# light_sensor_basic_finished.net
KiCad netlist of a schematic drawn in EAGLE
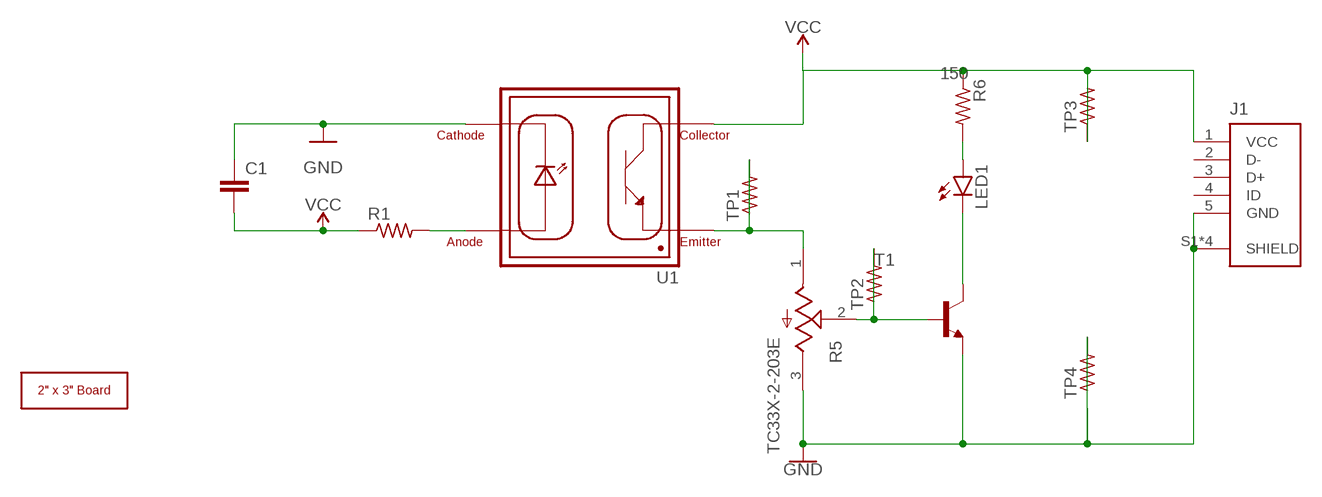
[diagram p0: schematic, sheet 1]

(export (version "E")
  (design (tool "Eeschema 10.0.6"))
  (components
    (comp (ref "C1")
      (value "1 uF")
      (footprint "eagle-import:C1206")
      (libsource (lib "eagle-import") (part "C-EUC1206"))
    )
    (comp (ref "J1")
      (value "UJ2-MIBH-G-SMT-TR")
      (footprint "eagle-import:CUI_UJ2-MIBH-G-SMT-TR")
      (fields (field (name "MANUFACTURER") "CUI"))
      (libsource (lib "eagle-import") (part "UJ2-MIBH-G-SMT-TR"))
    )
    (comp (ref "LED1")
      (value "LEDSML0805")
      (footprint "eagle-import:SML0805")
      (libsource (lib "eagle-import") (part "LEDSML0805"))
    )
    (comp (ref "R1")
      (value "R-US_M1206")
      (footprint "eagle-import:M1206")
      (libsource (lib "eagle-import") (part "R-US_M1206"))
    )
    (comp (ref "R5")
      (value "TC33X-2-203E")
      (footprint "eagle-import:TRIM_TC33X-2-203E")
      (fields (field (name "DIGIKEY_PART_NUMBER") "TC33X-2-203ETR-ND") (field (name "MF") "Bourns"))
      (libsource (lib "eagle-import") (part "TC33X-2-203E"))
    )
    (comp (ref "R6")
      (value "150")
      (footprint "eagle-import:M0805")
      (libsource (lib "eagle-import") (part "R-US_M0805"))
    )
    (comp (ref "T1")
      (value "-NPN-SOT23-EBC")
      (footprint "eagle-import:SOT23-EBC")
      (libsource (lib "eagle-import") (part "-NPN-SOT23-EBC"))
    )
    (comp (ref "TP1")
      (value "R-US_M1206")
      (footprint "eagle-import:M1206")
      (libsource (lib "eagle-import") (part "R-US_M1206"))
    )
    (comp (ref "TP2")
      (value "R-US_M1206")
      (footprint "eagle-import:M1206")
      (libsource (lib "eagle-import") (part "R-US_M1206"))
    )
    (comp (ref "TP3")
      (value "R-US_M1206")
      (footprint "eagle-import:M1206")
      (libsource (lib "eagle-import") (part "R-US_M1206"))
    )
    (comp (ref "TP4")
      (value "R-US_M1206")
      (footprint "eagle-import:M1206")
      (libsource (lib "eagle-import") (part "R-US_M1206"))
    )
    (comp (ref "U$1")
      (value "2X3_BOARD_V2")
      (footprint "eagle-import:2X3_BOARD_V2")
      (libsource (lib "eagle-import") (part "2X3_BOARD_V2"))
    )
    (comp (ref "U1")
      (value "VCNT2020")
      (footprint "eagle-import:XDCR_VCNT2020")
      (fields (field (name "DIGIKEY_PART_NUMBER") "VCNT2020TR-ND") (field (name "MF") "Vishay"))
      (libsource (lib "eagle-import") (part "VCNT2020"))
    )
  )
  (nets
    (net (code "1") (name "GND") (class "Default")
      (node (ref "C1") (pin "1") (pinfunction "1_1") (pintype "passive"))
      (node (ref "J1") (pin "5") (pinfunction "GND_5") (pintype "power_in"))
      (node (ref "J1") (pin "S1") (pinfunction "SHIELD_S1") (pintype "passive"))
      (node (ref "J1") (pin "S2") (pinfunction "SHIELD_S2") (pintype "passive"))
      (node (ref "J1") (pin "S3") (pinfunction "SHIELD_S3") (pintype "passive"))
      (node (ref "J1") (pin "S4") (pinfunction "SHIELD_S4") (pintype "passive"))
      (node (ref "R5") (pin "3") (pinfunction "CW_3") (pintype "passive"))
      (node (ref "T1") (pin "E") (pinfunction "E_E") (pintype "passive"))
      (node (ref "TP4") (pin "1") (pinfunction "1_1") (pintype "passive"))
      (node (ref "TP4") (pin "2") (pinfunction "2_2") (pintype "passive"))
      (node (ref "U1") (pin "4") (pinfunction "CATHODE_4") (pintype "passive"))
    )
    (net (code "2") (name "Net-(LED1-PadA)") (class "Default")
      (node (ref "LED1") (pin "A") (pinfunction "A_A") (pintype "passive"))
      (node (ref "R6") (pin "2") (pinfunction "2_2") (pintype "passive"))
    )
    (net (code "3") (name "Net-(LED1-PadC)") (class "Default")
      (node (ref "LED1") (pin "C") (pinfunction "C_C") (pintype "passive"))
      (node (ref "T1") (pin "C") (pinfunction "C_C") (pintype "passive"))
    )
    (net (code "4") (name "Net-(R5-CCW)") (class "Default")
      (node (ref "R5") (pin "1") (pinfunction "CCW_1") (pintype "passive"))
      (node (ref "TP1") (pin "1") (pinfunction "1_1") (pintype "passive"))
      (node (ref "TP1") (pin "2") (pinfunction "2_2") (pintype "passive"))
      (node (ref "U1") (pin "1") (pinfunction "EMITTER_1") (pintype "passive"))
    )
    (net (code "5") (name "Net-(R5-W)") (class "Default")
      (node (ref "R5") (pin "2") (pinfunction "W_2") (pintype "passive"))
      (node (ref "T1") (pin "B") (pinfunction "B_B") (pintype "passive"))
      (node (ref "TP2") (pin "1") (pinfunction "1_1") (pintype "passive"))
      (node (ref "TP2") (pin "2") (pinfunction "2_2") (pintype "passive"))
    )
    (net (code "6") (name "Net-(U1-ANODE)") (class "Default")
      (node (ref "R1") (pin "2") (pinfunction "2_2") (pintype "passive"))
      (node (ref "U1") (pin "3") (pinfunction "ANODE_3") (pintype "passive"))
    )
    (net (code "7") (name "VCC") (class "Default")
      (node (ref "C1") (pin "2") (pinfunction "2_2") (pintype "passive"))
      (node (ref "J1") (pin "1") (pinfunction "VCC_1") (pintype "power_in"))
      (node (ref "R1") (pin "1") (pinfunction "1_1") (pintype "passive"))
      (node (ref "R6") (pin "1") (pinfunction "1_1") (pintype "passive"))
      (node (ref "TP3") (pin "1") (pinfunction "1_1") (pintype "passive"))
      (node (ref "TP3") (pin "2") (pinfunction "2_2") (pintype "passive"))
      (node (ref "U1") (pin "2") (pinfunction "COLLECTOR_2") (pintype "passive"))
    )
    (net (code "8") (name "unconnected-(J1-D+-Pad3)") (class "Default")
      (node (ref "J1") (pin "3") (pinfunction "D+_3") (pintype "bidirectional"))
    )
    (net (code "9") (name "unconnected-(J1-D--Pad2)") (class "Default")
      (node (ref "J1") (pin "2") (pinfunction "D-_2") (pintype "bidirectional"))
    )
    (net (code "10") (name "unconnected-(J1-ID-Pad4)") (class "Default")
      (node (ref "J1") (pin "4") (pinfunction "ID_4") (pintype "bidirectional"))
    )
  )
)
